# HearingAid.net
KiCad netlist of a schematic drawn in Altium Designer
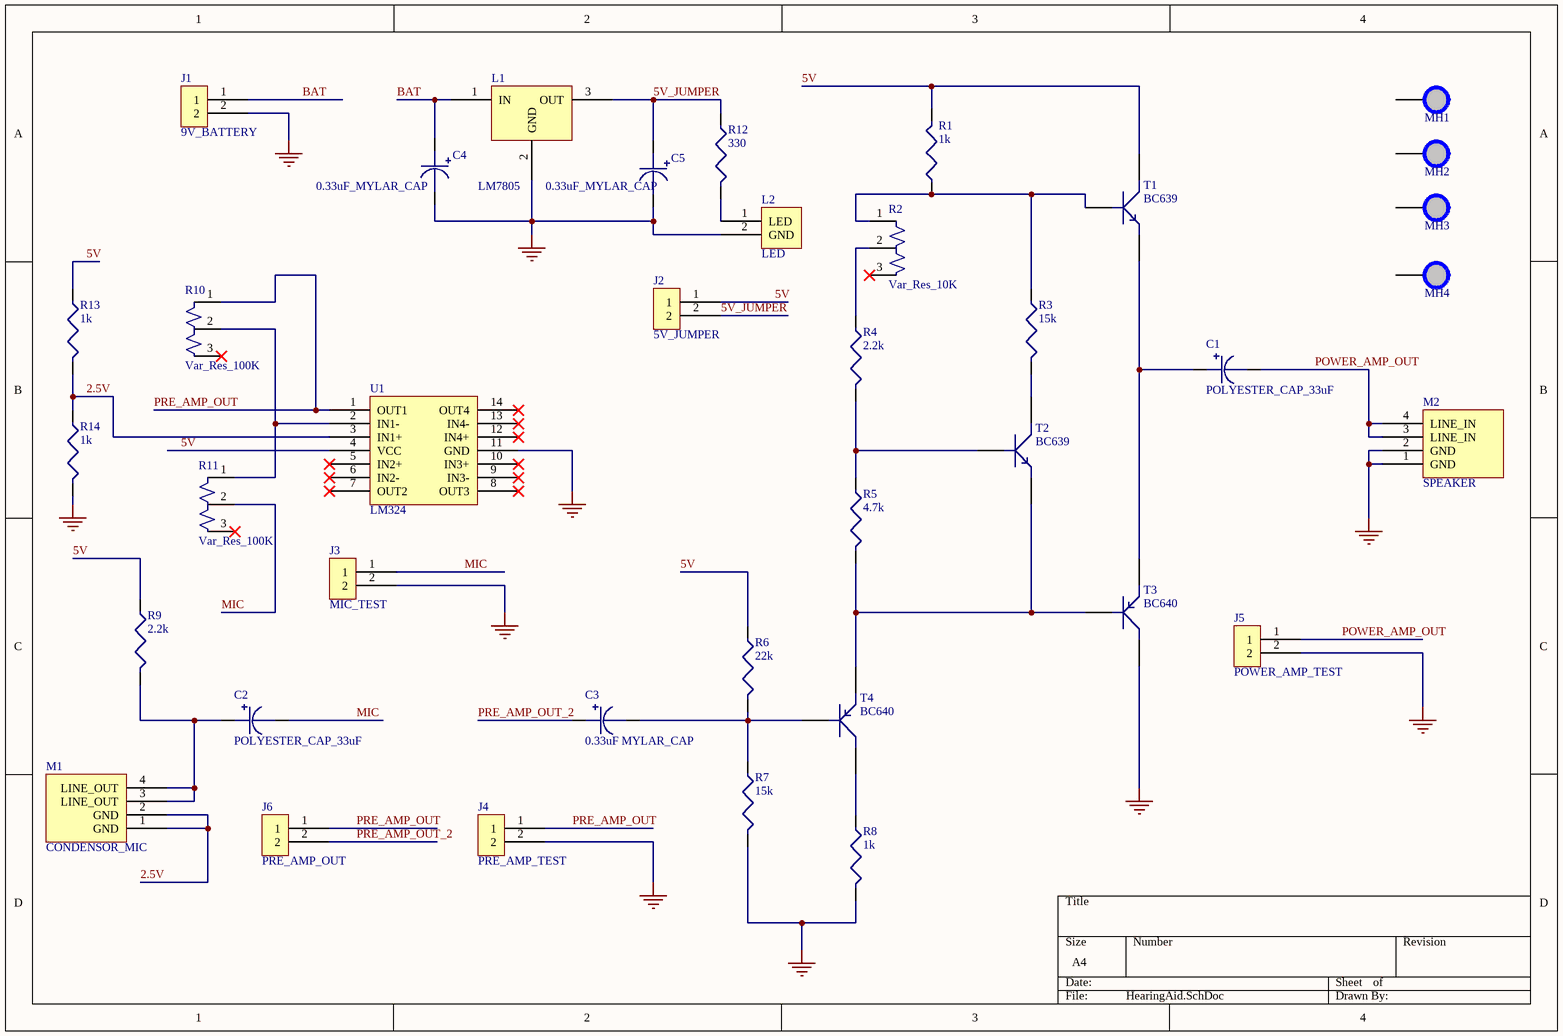
[diagram p0: HearingAid.SchDoc]

(export (version "E")
  (design (tool "Eeschema 10.0.6"))
  (components
    (comp (ref "C1")
      (value "POLYESTER_CAP_33uF")
      (footprint "POLYESTER_CAP2")
      (libsource (lib "Components_2") (part "POLYESTER_CAP2"))
    )
    (comp (ref "C2")
      (value "POLYESTER_CAP_33uF")
      (footprint "POLYESTER_CAP2")
      (libsource (lib "Components_2") (part "POLYESTER_CAP2"))
    )
    (comp (ref "C3")
      (value "0.33uF MYLAR_CAP")
      (footprint "POLYESTER_CAP2")
      (libsource (lib "Components_2") (part "POLYESTER_CAP2"))
    )
    (comp (ref "C4")
      (value "0.33uF_MYLAR_CAP")
      (footprint "POLYESTER_CAP2")
      (libsource (lib "Components_2") (part "POLYESTER_CAP2"))
    )
    (comp (ref "C5")
      (value "0.33uF_MYLAR_CAP")
      (footprint "POLYESTER_CAP2")
      (libsource (lib "Components_2") (part "POLYESTER_CAP2"))
    )
    (comp (ref "J1")
      (value "9V_BATTERY")
      (footprint "HEADER_MALE_2_POS")
      (libsource (lib "Components_2") (part "HEADER_MALE_2_POS"))
    )
    (comp (ref "J2")
      (value "5V_JUMPER")
      (footprint "HEADER_MALE_2_POS")
      (libsource (lib "Components_2") (part "HEADER_MALE_2_POS"))
    )
    (comp (ref "J3")
      (value "MIC_TEST")
      (footprint "HEADER_MALE_2_POS")
      (libsource (lib "Components_2") (part "HEADER_MALE_2_POS"))
    )
    (comp (ref "J4")
      (value "PRE_AMP_TEST")
      (footprint "HEADER_MALE_2_POS")
      (libsource (lib "Components_2") (part "HEADER_MALE_2_POS"))
    )
    (comp (ref "J5")
      (value "POWER_AMP_TEST")
      (footprint "HEADER_MALE_2_POS")
      (libsource (lib "Components_2") (part "HEADER_MALE_2_POS"))
    )
    (comp (ref "J6")
      (value "PRE_AMP_OUT")
      (footprint "HEADER_MALE_2_POS")
      (libsource (lib "Components_2") (part "HEADER_MALE_2_POS"))
    )
    (comp (ref "L1") (value "LM7805") (footprint "LM7805") (libsource (lib "Components_2") (part "LM7805")))
    (comp (ref "L2") (value "LED") (footprint "LED_3mm") (libsource (lib "Components_2") (part "LED")))
    (comp (ref "M1")
      (value "CONDENSOR_MIC")
      (footprint "CONDENSOR_MIC")
      (libsource (lib "Components_2") (part "CONDENSOR_MIC"))
    )
    (comp (ref "M2")
      (value "SPEAKER")
      (footprint "SPEAKER")
      (libsource (lib "Components_2") (part "SPEAKER"))
    )
    (comp (ref "MH1")
      (value "MOUNTING_HOLE_3mm_NON_PLATED")
      (footprint "MOUNTING_HOLE_3mm_NONPLATED")
      (libsource (lib "Components_UNO") (part "MOUNTING_HOLE_3mm_NON_PLATED"))
    )
    (comp (ref "MH2")
      (value "MOUNTING_HOLE_3mm_NON_PLATED")
      (footprint "MOUNTING_HOLE_3mm_NONPLATED")
      (libsource (lib "Components_UNO") (part "MOUNTING_HOLE_3mm_NON_PLATED"))
    )
    (comp (ref "MH3")
      (value "MOUNTING_HOLE_3mm_NON_PLATED")
      (footprint "MOUNTING_HOLE_3mm_NONPLATED")
      (libsource (lib "Components_UNO") (part "MOUNTING_HOLE_3mm_NON_PLATED"))
    )
    (comp (ref "MH4")
      (value "MOUNTING_HOLE_3mm_NON_PLATED")
      (footprint "MOUNTING_HOLE_3mm_NONPLATED")
      (libsource (lib "Components_UNO") (part "MOUNTING_HOLE_3mm_NON_PLATED"))
    )
    (comp (ref "R1") (value "1k") (footprint "Axial_Res") (libsource (lib "Components_2") (part "Axial_Res")))
    (comp (ref "R2")
      (value "Var_Res_10K")
      (footprint "TRIMMER_10K")
      (fields
        (field (name "MANUFACTURER") "Bourns")
        (field (name "MANUFACTURER PART NUMBER") "3292W-1-103MLF")
        (field (name "TOLERANCE") "10 %")
      )
      (libsource (lib "Components_2") (part "TRIMMER_10K"))
    )
    (comp (ref "R3")
      (value "15k")
      (footprint "Axial_Res")
      (libsource (lib "Components_2") (part "Axial_Res"))
    )
    (comp (ref "R4")
      (value "2.2k")
      (footprint "Axial_Res")
      (libsource (lib "Components_2") (part "Axial_Res"))
    )
    (comp (ref "R5")
      (value "4.7k")
      (footprint "Axial_Res")
      (libsource (lib "Components_2") (part "Axial_Res"))
    )
    (comp (ref "R6")
      (value "22k")
      (footprint "Axial_Res")
      (libsource (lib "Components_2") (part "Axial_Res"))
    )
    (comp (ref "R7")
      (value "15k")
      (footprint "Axial_Res")
      (libsource (lib "Components_2") (part "Axial_Res"))
    )
    (comp (ref "R8") (value "1k") (footprint "Axial_Res") (libsource (lib "Components_2") (part "Axial_Res")))
    (comp (ref "R9")
      (value "2.2k")
      (footprint "Axial_Res")
      (libsource (lib "Components_2") (part "Axial_Res"))
    )
    (comp (ref "R10")
      (value "Var_Res_100K")
      (footprint "TRIMMER_10K")
      (fields
        (field (name "MANUFACTURER") "Bourns")
        (field (name "MANUFACTURER PART NUMBER") "3292W-1-103MLF")
        (field (name "TOLERANCE") "10 %")
      )
      (libsource (lib "Components_2") (part "TRIMMER_10K"))
    )
    (comp (ref "R11")
      (value "Var_Res_100K")
      (footprint "TRIMMER_10K")
      (fields
        (field (name "MANUFACTURER") "Bourns")
        (field (name "MANUFACTURER PART NUMBER") "3292W-1-103MLF")
        (field (name "TOLERANCE") "10 %")
      )
      (libsource (lib "Components_2") (part "TRIMMER_10K"))
    )
    (comp (ref "R12")
      (value "330")
      (footprint "Axial_Res")
      (libsource (lib "Components_2") (part "Axial_Res"))
    )
    (comp (ref "R13")
      (value "1k")
      (footprint "Axial_Res")
      (libsource (lib "Components_2") (part "Axial_Res"))
    )
    (comp (ref "R14")
      (value "1k")
      (footprint "Axial_Res")
      (libsource (lib "Components_2") (part "Axial_Res"))
    )
    (comp (ref "T1") (value "BC639") (footprint "BC639") (libsource (lib "Components_2") (part "BC639")))
    (comp (ref "T2") (value "BC639") (footprint "BC639") (libsource (lib "Components_2") (part "BC639")))
    (comp (ref "T3") (value "BC640") (footprint "BC640") (libsource (lib "Components_2") (part "BC640")))
    (comp (ref "T4") (value "BC640") (footprint "BC640") (libsource (lib "Components_2") (part "BC640")))
    (comp (ref "U1") (value "LM324") (footprint "LM324") (libsource (lib "Components_2") (part "LM324")))
  )
  (nets
    (net (code "1") (name "/2.5V") (class "Default")
      (node (ref "M1") (pin "1") (pinfunction "GND_1") (pintype "passive"))
      (node (ref "M1") (pin "2") (pinfunction "GND_2") (pintype "passive"))
      (node (ref "R13") (pin "2") (pinfunction "2_2") (pintype "passive"))
      (node (ref "R14") (pin "1") (pinfunction "1_1") (pintype "passive"))
      (node (ref "U1") (pin "3") (pinfunction "IN1+_3") (pintype "passive"))
    )
    (net (code "2") (name "/5V") (class "Default")
      (node (ref "J2") (pin "1") (pinfunction "1_1") (pintype "passive"))
      (node (ref "R1") (pin "2") (pinfunction "2_2") (pintype "passive"))
      (node (ref "R13") (pin "1") (pinfunction "1_1") (pintype "passive"))
      (node (ref "R6") (pin "1") (pinfunction "1_1") (pintype "passive"))
      (node (ref "R9") (pin "1") (pinfunction "1_1") (pintype "passive"))
      (node (ref "T1") (pin "2") (pinfunction "2_2") (pintype "passive"))
      (node (ref "U1") (pin "4") (pinfunction "VCC_4") (pintype "passive"))
    )
    (net (code "3") (name "/5V_JUMPER") (class "Default")
      (node (ref "C5") (pin "1") (pinfunction "1_1") (pintype "passive"))
      (node (ref "J2") (pin "2") (pinfunction "2_2") (pintype "passive"))
      (node (ref "L1") (pin "3") (pinfunction "OUT_3") (pintype "passive"))
      (node (ref "R12") (pin "1") (pinfunction "1_1") (pintype "passive"))
    )
    (net (code "4") (name "/BAT") (class "Default")
      (node (ref "C4") (pin "1") (pinfunction "1_1") (pintype "passive"))
      (node (ref "J1") (pin "1") (pinfunction "1_1") (pintype "passive"))
      (node (ref "L1") (pin "1") (pinfunction "IN_1") (pintype "passive"))
    )
    (net (code "5") (name "/MIC") (class "Default")
      (node (ref "C2") (pin "2") (pinfunction "2_2") (pintype "passive"))
      (node (ref "J3") (pin "1") (pinfunction "1_1") (pintype "passive"))
      (node (ref "R11") (pin "2") (pinfunction "2_2") (pintype "passive"))
    )
    (net (code "6") (name "/POWER_AMP_OUT") (class "Default")
      (node (ref "C1") (pin "2") (pinfunction "2_2") (pintype "passive"))
      (node (ref "J5") (pin "1") (pinfunction "1_1") (pintype "passive"))
      (node (ref "M2") (pin "3") (pinfunction "LINE_IN_3") (pintype "passive"))
      (node (ref "M2") (pin "4") (pinfunction "LINE_IN_4") (pintype "passive"))
    )
    (net (code "7") (name "/PRE_AMP_OUT") (class "Default")
      (node (ref "J4") (pin "1") (pinfunction "1_1") (pintype "passive"))
      (node (ref "J6") (pin "1") (pinfunction "1_1") (pintype "passive"))
      (node (ref "R10") (pin "1") (pinfunction "1_1") (pintype "passive"))
      (node (ref "U1") (pin "1") (pinfunction "OUT1_1") (pintype "passive"))
    )
    (net (code "8") (name "/PRE_AMP_OUT_2") (class "Default")
      (node (ref "C3") (pin "1") (pinfunction "1_1") (pintype "passive"))
      (node (ref "J6") (pin "2") (pinfunction "2_2") (pintype "passive"))
    )
    (net (code "9") (name "GND") (class "Default")
      (node (ref "C4") (pin "2") (pinfunction "2_2") (pintype "passive"))
      (node (ref "C5") (pin "2") (pinfunction "2_2") (pintype "passive"))
      (node (ref "J1") (pin "2") (pinfunction "2_2") (pintype "passive"))
      (node (ref "J3") (pin "2") (pinfunction "2_2") (pintype "passive"))
      (node (ref "J4") (pin "2") (pinfunction "2_2") (pintype "passive"))
      (node (ref "J5") (pin "2") (pinfunction "2_2") (pintype "passive"))
      (node (ref "L1") (pin "2") (pinfunction "GND_2") (pintype "passive"))
      (node (ref "L2") (pin "2") (pinfunction "GND_2") (pintype "passive"))
      (node (ref "M2") (pin "1") (pinfunction "GND_1") (pintype "passive"))
      (node (ref "M2") (pin "2") (pinfunction "GND_2") (pintype "passive"))
      (node (ref "R14") (pin "2") (pinfunction "2_2") (pintype "passive"))
      (node (ref "R7") (pin "2") (pinfunction "2_2") (pintype "passive"))
      (node (ref "R8") (pin "2") (pinfunction "2_2") (pintype "passive"))
      (node (ref "T3") (pin "2") (pinfunction "2_2") (pintype "passive"))
      (node (ref "U1") (pin "11") (pinfunction "GND_11") (pintype "passive"))
    )
    (net (code "10") (name "Net-(C1-Pad1)") (class "Default")
      (node (ref "C1") (pin "1") (pinfunction "1_1") (pintype "passive"))
      (node (ref "T1") (pin "1") (pinfunction "1_1") (pintype "passive"))
      (node (ref "T3") (pin "1") (pinfunction "1_1") (pintype "passive"))
    )
    (net (code "11") (name "Net-(C2-Pad1)") (class "Default")
      (node (ref "C2") (pin "1") (pinfunction "1_1") (pintype "passive"))
      (node (ref "M1") (pin "3") (pinfunction "LINE_OUT_3") (pintype "passive"))
      (node (ref "M1") (pin "4") (pinfunction "LINE_OUT_4") (pintype "passive"))
      (node (ref "R9") (pin "2") (pinfunction "2_2") (pintype "passive"))
    )
    (net (code "12") (name "Net-(C3-Pad2)") (class "Default")
      (node (ref "C3") (pin "2") (pinfunction "2_2") (pintype "passive"))
      (node (ref "R6") (pin "2") (pinfunction "2_2") (pintype "passive"))
      (node (ref "R7") (pin "1") (pinfunction "1_1") (pintype "passive"))
      (node (ref "T4") (pin "3") (pinfunction "3_3") (pintype "passive"))
    )
    (net (code "13") (name "Net-(L2-LED)") (class "Default")
      (node (ref "L2") (pin "1") (pinfunction "LED_1") (pintype "passive"))
      (node (ref "R12") (pin "2") (pinfunction "2_2") (pintype "passive"))
    )
    (net (code "14") (name "Net-(R1-Pad1)") (class "Default")
      (node (ref "R1") (pin "1") (pinfunction "1_1") (pintype "passive"))
      (node (ref "R2") (pin "1") (pinfunction "1_1") (pintype "passive"))
      (node (ref "R3") (pin "1") (pinfunction "1_1") (pintype "passive"))
      (node (ref "T1") (pin "3") (pinfunction "3_3") (pintype "passive"))
    )
    (net (code "15") (name "Net-(R2-Pad2)") (class "Default")
      (node (ref "R2") (pin "2") (pinfunction "2_2") (pintype "passive"))
      (node (ref "R4") (pin "1") (pinfunction "1_1") (pintype "passive"))
    )
    (net (code "16") (name "Net-(R3-Pad2)") (class "Default")
      (node (ref "R3") (pin "2") (pinfunction "2_2") (pintype "passive"))
      (node (ref "T2") (pin "2") (pinfunction "2_2") (pintype "passive"))
    )
    (net (code "17") (name "Net-(R4-Pad2)") (class "Default")
      (node (ref "R4") (pin "2") (pinfunction "2_2") (pintype "passive"))
      (node (ref "R5") (pin "1") (pinfunction "1_1") (pintype "passive"))
      (node (ref "T2") (pin "3") (pinfunction "3_3") (pintype "passive"))
    )
    (net (code "18") (name "Net-(R5-Pad2)") (class "Default")
      (node (ref "R5") (pin "2") (pinfunction "2_2") (pintype "passive"))
      (node (ref "T2") (pin "1") (pinfunction "1_1") (pintype "passive"))
      (node (ref "T3") (pin "3") (pinfunction "3_3") (pintype "passive"))
      (node (ref "T4") (pin "1") (pinfunction "1_1") (pintype "passive"))
    )
    (net (code "19") (name "Net-(R8-Pad1)") (class "Default")
      (node (ref "R8") (pin "1") (pinfunction "1_1") (pintype "passive"))
      (node (ref "T4") (pin "2") (pinfunction "2_2") (pintype "passive"))
    )
    (net (code "20") (name "Net-(U1-IN1-)") (class "Default")
      (node (ref "R10") (pin "2") (pinfunction "2_2") (pintype "passive"))
      (node (ref "R11") (pin "1") (pinfunction "1_1") (pintype "passive"))
      (node (ref "U1") (pin "2") (pinfunction "IN1-_2") (pintype "passive"))
    )
    (net (code "21") (name "unconnected-(MH1-Pad1)") (class "Default")
      (node (ref "MH1") (pin "1") (pinfunction "1_1") (pintype "passive"))
    )
    (net (code "22") (name "unconnected-(MH2-Pad1)") (class "Default")
      (node (ref "MH2") (pin "1") (pinfunction "1_1") (pintype "passive"))
    )
    (net (code "23") (name "unconnected-(MH3-Pad1)") (class "Default")
      (node (ref "MH3") (pin "1") (pinfunction "1_1") (pintype "passive"))
    )
    (net (code "24") (name "unconnected-(MH4-Pad1)") (class "Default")
      (node (ref "MH4") (pin "1") (pinfunction "1_1") (pintype "passive"))
    )
    (net (code "25") (name "unconnected-(R2-Pad3)") (class "Default")
      (node (ref "R2") (pin "3") (pinfunction "3_3") (pintype "passive+no_connect"))
    )
    (net (code "26") (name "unconnected-(R10-Pad3)") (class "Default")
      (node (ref "R10") (pin "3") (pinfunction "3_3") (pintype "passive+no_connect"))
    )
    (net (code "27") (name "unconnected-(R11-Pad3)") (class "Default")
      (node (ref "R11") (pin "3") (pinfunction "3_3") (pintype "passive+no_connect"))
    )
    (net (code "28") (name "unconnected-(U1-IN2+-Pad5)") (class "Default")
      (node (ref "U1") (pin "5") (pinfunction "IN2+_5") (pintype "passive+no_connect"))
    )
    (net (code "29") (name "unconnected-(U1-IN2--Pad6)") (class "Default")
      (node (ref "U1") (pin "6") (pinfunction "IN2-_6") (pintype "passive+no_connect"))
    )
    (net (code "30") (name "unconnected-(U1-IN3+-Pad10)") (class "Default")
      (node (ref "U1") (pin "10") (pinfunction "IN3+_10") (pintype "passive+no_connect"))
    )
    (net (code "31") (name "unconnected-(U1-IN3--Pad9)") (class "Default")
      (node (ref "U1") (pin "9") (pinfunction "IN3-_9") (pintype "passive+no_connect"))
    )
    (net (code "32") (name "unconnected-(U1-IN4+-Pad12)") (class "Default")
      (node (ref "U1") (pin "12") (pinfunction "IN4+_12") (pintype "passive+no_connect"))
    )
    (net (code "33") (name "unconnected-(U1-IN4--Pad13)") (class "Default")
      (node (ref "U1") (pin "13") (pinfunction "IN4-_13") (pintype "passive+no_connect"))
    )
    (net (code "34") (name "unconnected-(U1-OUT2-Pad7)") (class "Default")
      (node (ref "U1") (pin "7") (pinfunction "OUT2_7") (pintype "passive+no_connect"))
    )
    (net (code "35") (name "unconnected-(U1-OUT3-Pad8)") (class "Default")
      (node (ref "U1") (pin "8") (pinfunction "OUT3_8") (pintype "passive+no_connect"))
    )
    (net (code "36") (name "unconnected-(U1-OUT4-Pad14)") (class "Default")
      (node (ref "U1") (pin "14") (pinfunction "OUT4_14") (pintype "passive+no_connect"))
    )
  )
)
